# 3_Radio.net
KiCad netlist of a schematic drawn in Altium Designer
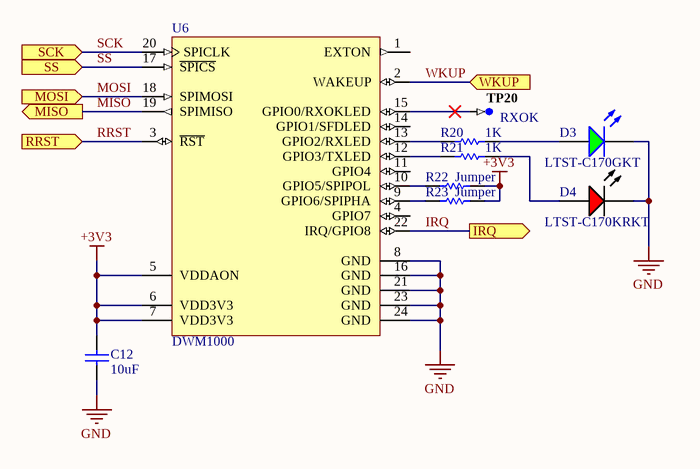
[diagram p0: 3_Radio.SchDoc]

(export (version "E")
  (design (tool "Eeschema 10.0.6"))
  (components
    (comp (ref "C12")
      (value "10uF")
      (footprint "CAPC1206(3216)130_L")
      (description "CAP 10uF 16V -20% to +80% 1206 (3216 Metric) Thickness 1.3mm SMD")
      (fields (field (name "TOLERANCE") "-20% to +80%"))
      (libsource (lib "Altium Content Vault") (part "CAP"))
    )
    (comp (ref "D3")
      (value "LTST-C170GKT")
      (footprint "LTST-C170GKT_V")
      (description "LED GREEN CLEAR 0805 SMD")
      (fields (field (name "MANUFACTURER") "Lite-On"))
      (libsource (lib "Altium Content Vault") (part "LED_GREEN_AC"))
    )
    (comp (ref "D4")
      (value "LTST-C170KRKT")
      (footprint "LTST-C170KRKT_V")
      (description "LED Red, 75 mW, 54 mcd, -55 to 85 degC, 2-Pin SMD, RoHS, Tape and Reel")
      (fields (field (name "MANUFACTURER") "Lite-On"))
      (libsource (lib "Altium Content Vault") (part "LED-RED-AK-2"))
    )
    (comp (ref "R20")
      (value "1K")
      (footprint "RESC0603(1608)_M")
      (description "1K 0.1W 1% 0603 (1608 Metric)  SMD")
      (fields (field (name "TOLERANCE") "1 %") (field (name "POWER") "0.1 W"))
      (libsource (lib "Altium Content Vault") (part "RES"))
    )
    (comp (ref "R21")
      (value "1K")
      (footprint "RESC0603(1608)_M")
      (description "1K 0.1W 1% 0603 (1608 Metric)  SMD")
      (fields (field (name "TOLERANCE") "1 %") (field (name "POWER") "0.1 W"))
      (libsource (lib "Altium Content Vault") (part "RES"))
    )
    (comp (ref "R22")
      (value "Jumper")
      (footprint "RESC0805(2012)_M")
      (description "Jumper 0805 (2012 Metric)")
      (fields (field (name "TOLERANCE") "None"))
      (libsource (lib "Altium Content Vault") (part "RES"))
    )
    (comp (ref "R23")
      (value "Jumper")
      (footprint "RESC0805(2012)_M")
      (description "Jumper 0805 (2012 Metric)")
      (fields (field (name "TOLERANCE") "None"))
      (libsource (lib "Altium Content Vault") (part "RES"))
    )
    (comp (ref "TP20")
      (value "RXOK")
      (footprint "TP-SM-C-100")
      (description "Test Point, Surface Mount, Circular, Pad Diameter 1 mm")
      (fields (field (name "PARTNUMBER") "TP-SM-C-100") (field (name "MANUFACTURER") "No Vendor"))
      (libsource (lib "Altium Content Vault") (part "TP-SM"))
    )
    (comp (ref "U6")
      (value "DWM1000")
      (footprint "DECW-DWM1000-24_V")
      (description "DW M1000 IEEE 802.15.4 -2011 UWB Transceiver Module")
      (fields (field (name "MANUFACTURER") "Decawave"))
      (libsource (lib "Altium Content Vault") (part "DECW-DWM1000-24"))
    )
  )
  (nets
    (net (code "1") (name "+3V3") (class "Default")
      (node (ref "C12") (pin "2") (pinfunction "2_2") (pintype "passive"))
      (node (ref "R22") (pin "1") (pinfunction "1_1") (pintype "passive"))
      (node (ref "R23") (pin "1") (pinfunction "1_1") (pintype "passive"))
      (node (ref "U6") (pin "5") (pinfunction "VDDAON_5") (pintype "power_in"))
      (node (ref "U6") (pin "6") (pinfunction "VDD3V3_6") (pintype "power_in"))
      (node (ref "U6") (pin "7") (pinfunction "VDD3V3_7") (pintype "power_in"))
    )
    (net (code "2") (name "/IRQ") (class "Default")
      (node (ref "U6") (pin "22") (pinfunction "IRQ/GPIO8_22") (pintype "bidirectional"))
    )
    (net (code "3") (name "/MISO") (class "Default")
      (node (ref "U6") (pin "19") (pinfunction "SPIMISO_19") (pintype "output"))
    )
    (net (code "4") (name "/MOSI") (class "Default")
      (node (ref "U6") (pin "18") (pinfunction "SPIMOSI_18") (pintype "input"))
    )
    (net (code "5") (name "/RRST") (class "Default")
      (node (ref "U6") (pin "3") (pinfunction "~{RST}_3") (pintype "bidirectional"))
    )
    (net (code "6") (name "/SCK") (class "Default")
      (node (ref "U6") (pin "20") (pinfunction "SPICLK_20") (pintype "input"))
    )
    (net (code "7") (name "/SS") (class "Default")
      (node (ref "U6") (pin "17") (pinfunction "~{SPICS}_17") (pintype "input"))
    )
    (net (code "8") (name "/WKUP") (class "Default")
      (node (ref "U6") (pin "2") (pinfunction "WAKEUP_2") (pintype "bidirectional"))
    )
    (net (code "9") (name "GND") (class "Default")
      (node (ref "C12") (pin "1") (pinfunction "1_1") (pintype "passive"))
      (node (ref "D3") (pin "C") (pinfunction "C_C") (pintype "passive"))
      (node (ref "D4") (pin "2") (pinfunction "K_2") (pintype "passive"))
      (node (ref "U6") (pin "16") (pinfunction "GND_16") (pintype "power_in"))
      (node (ref "U6") (pin "21") (pinfunction "GND_21") (pintype "power_in"))
      (node (ref "U6") (pin "23") (pinfunction "GND_23") (pintype "power_in"))
      (node (ref "U6") (pin "24") (pinfunction "GND_24") (pintype "power_in"))
      (node (ref "U6") (pin "8") (pinfunction "GND_8") (pintype "power_in"))
    )
    (net (code "10") (name "Net-(D3-PadA)") (class "Default")
      (node (ref "D3") (pin "A") (pinfunction "A_A") (pintype "passive"))
      (node (ref "R20") (pin "1") (pinfunction "1_1") (pintype "passive"))
    )
    (net (code "11") (name "Net-(D4-A)") (class "Default")
      (node (ref "D4") (pin "1") (pinfunction "A_1") (pintype "passive"))
      (node (ref "R21") (pin "1") (pinfunction "1_1") (pintype "passive"))
    )
    (net (code "12") (name "Net-(U6-GPIO0{slash}RXOKLED)") (class "Default")
      (node (ref "TP20") (pin "1") (pinfunction "1_1") (pintype "input"))
      (node (ref "U6") (pin "15") (pinfunction "GPIO0/RXOKLED_15") (pintype "bidirectional"))
    )
    (net (code "13") (name "Net-(U6-GPIO2{slash}RXLED)") (class "Default")
      (node (ref "R20") (pin "2") (pinfunction "2_2") (pintype "passive"))
      (node (ref "U6") (pin "13") (pinfunction "GPIO2/RXLED_13") (pintype "bidirectional"))
    )
    (net (code "14") (name "Net-(U6-GPIO3{slash}TXLED)") (class "Default")
      (node (ref "R21") (pin "2") (pinfunction "2_2") (pintype "passive"))
      (node (ref "U6") (pin "12") (pinfunction "GPIO3/TXLED_12") (pintype "bidirectional"))
    )
    (net (code "15") (name "Net-(U6-GPIO5{slash}SPIPOL)") (class "Default")
      (node (ref "R22") (pin "2") (pinfunction "2_2") (pintype "passive"))
      (node (ref "U6") (pin "10") (pinfunction "GPIO5/SPIPOL_10") (pintype "bidirectional"))
    )
    (net (code "16") (name "Net-(U6-GPIO6{slash}SPIPHA)") (class "Default")
      (node (ref "R23") (pin "2") (pinfunction "2_2") (pintype "passive"))
      (node (ref "U6") (pin "9") (pinfunction "GPIO6/SPIPHA_9") (pintype "bidirectional"))
    )
    (net (code "17") (name "unconnected-(U6-EXTON-Pad1)") (class "Default")
      (node (ref "U6") (pin "1") (pinfunction "EXTON_1") (pintype "output"))
    )
    (net (code "18") (name "unconnected-(U6-GPIO1{slash}SFDLED-Pad14)") (class "Default")
      (node (ref "U6") (pin "14") (pinfunction "GPIO1/SFDLED_14") (pintype "bidirectional"))
    )
    (net (code "19") (name "unconnected-(U6-GPIO4-Pad11)") (class "Default")
      (node (ref "U6") (pin "11") (pinfunction "GPIO4_11") (pintype "bidirectional"))
    )
    (net (code "20") (name "unconnected-(U6-GPIO7-Pad4)") (class "Default")
      (node (ref "U6") (pin "4") (pinfunction "GPIO7_4") (pintype "bidirectional"))
    )
  )
)
